# lv_power.net
KiCad netlist of a schematic drawn in EAGLE
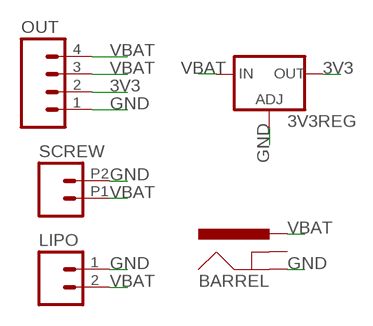
[diagram p0: schematic, sheet 1]

(export (version "E")
  (design (tool "Eeschema 10.0.6"))
  (components
    (comp (ref "3V3REG")
      (value "V_REG_317DPACK")
      (footprint "eagle-import:V-REG_DPACK")
      (libsource (lib "eagle-import") (part "V_REG_317DPACK"))
    )
    (comp (ref "BARREL")
      (value "POWER_JACKPTH_BREAD")
      (footprint "eagle-import:POWER_JACK_PTH_BREAD")
      (libsource (lib "eagle-import") (part "POWER_JACKPTH_BREAD"))
    )
    (comp (ref "LIPO")
      (value "M02-JST-2MM-SMT")
      (footprint "eagle-import:JST-2-SMD")
      (libsource (lib "eagle-import") (part "M02-JST-2MM-SMT"))
    )
    (comp (ref "OUT")
      (value "M04PTH")
      (footprint "eagle-import:1X04")
      (libsource (lib "eagle-import") (part "M04PTH"))
    )
    (comp (ref "SCREW")
      (value "M022.54MM_SCREWTERM")
      (footprint "eagle-import:1X02_2.54_SCREWTERM")
      (libsource (lib "eagle-import") (part "M022.54MM_SCREWTERM"))
    )
  )
  (nets
    (net (code "1") (name "/3V3") (class "Default")
      (node (ref "3V3REG") (pin "4") (pinfunction "OUT_4") (pintype "output"))
      (node (ref "OUT") (pin "2") (pinfunction "2_2") (pintype "passive"))
    )
    (net (code "2") (name "/GND") (class "Default")
      (node (ref "3V3REG") (pin "1") (pinfunction "ADJ_1") (pintype "input"))
      (node (ref "BARREL") (pin "GND") (pinfunction "GND_GND") (pintype "bidirectional"))
      (node (ref "LIPO") (pin "1") (pinfunction "2_1") (pintype "passive"))
      (node (ref "OUT") (pin "1") (pinfunction "1_1") (pintype "passive"))
      (node (ref "SCREW") (pin "P2") (pinfunction "2_P2") (pintype "passive"))
    )
    (net (code "3") (name "/VBAT") (class "Default")
      (node (ref "3V3REG") (pin "3") (pinfunction "IN_3") (pintype "input"))
      (node (ref "BARREL") (pin "PWR") (pinfunction "PWR_PWR") (pintype "bidirectional"))
      (node (ref "LIPO") (pin "2") (pinfunction "1_2") (pintype "passive"))
      (node (ref "OUT") (pin "3") (pinfunction "3_3") (pintype "passive"))
      (node (ref "OUT") (pin "4") (pinfunction "4_4") (pintype "passive"))
      (node (ref "SCREW") (pin "P1") (pinfunction "1_P1") (pintype "passive"))
    )
    (net (code "4") (name "unconnected-(BARREL-PadGNDBREAK)") (class "Default")
      (node (ref "BARREL") (pin "GNDBREAK") (pinfunction "GNDBREAK_GNDBREAK") (pintype "bidirectional"))
    )
  )
)
